# ART-Pi_Power.net
KiCad netlist of a schematic drawn in Altium Designer
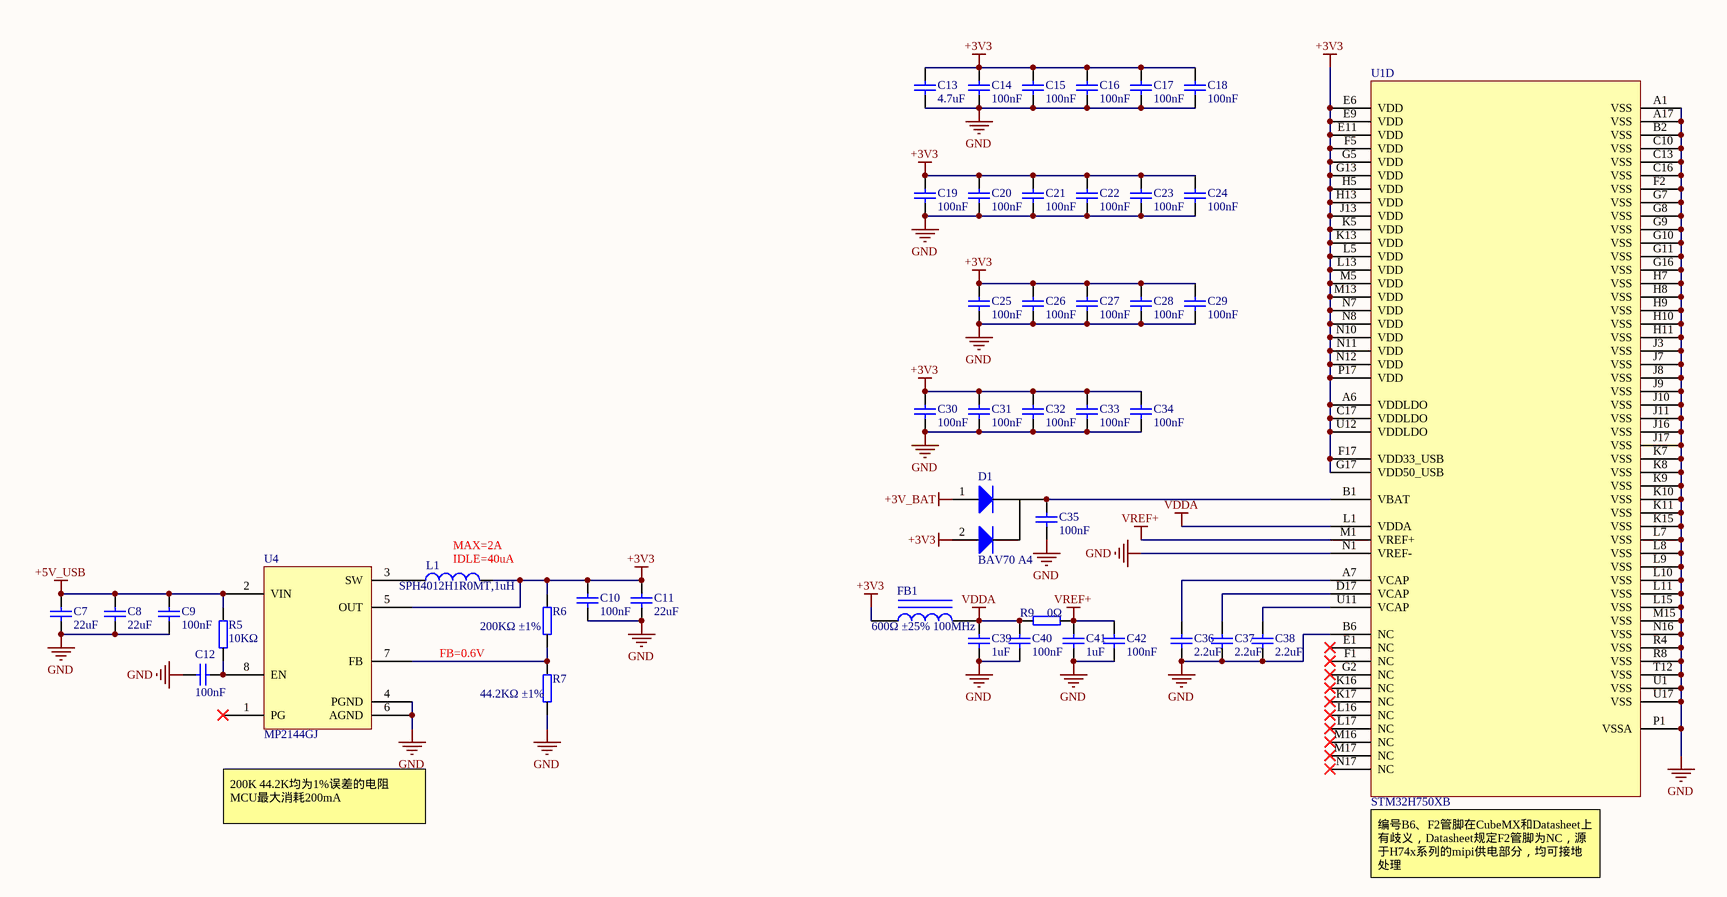
[diagram p0: ART-Pi_Power.SchDoc]

(export (version "E")
  (design (tool "Eeschema 10.0.6"))
  (components
    (comp (ref "C7")
      (value "22uF")
      (footprint "0603_C")
      (description "Capacitor")
      (fields (field (name "PUBLISHER") "Altium Limited"))
      (libsource (lib "ART-Pi_STM32H750_COPY") (part "Cap"))
    )
    (comp (ref "C8")
      (value "22uF")
      (footprint "0603_C")
      (description "Capacitor")
      (fields (field (name "PUBLISHER") "Altium Limited"))
      (libsource (lib "ART-Pi_STM32H750_COPY") (part "Cap"))
    )
    (comp (ref "C9")
      (value "100nF")
      (footprint "0402_C")
      (description "Capacitor")
      (fields (field (name "PUBLISHER") "Altium Limited"))
      (libsource (lib "ART-Pi_STM32H750_COPY") (part "Cap"))
    )
    (comp (ref "C10")
      (value "100nF")
      (footprint "0402_C")
      (description "Capacitor")
      (fields (field (name "PUBLISHER") "Altium Limited"))
      (libsource (lib "ART-Pi_STM32H750_COPY") (part "Cap"))
    )
    (comp (ref "C11")
      (value "22uF")
      (footprint "0603_C")
      (description "Capacitor")
      (fields (field (name "PUBLISHER") "Altium Limited"))
      (libsource (lib "ART-Pi_STM32H750_COPY") (part "Cap"))
    )
    (comp (ref "C12")
      (value "100nF")
      (footprint "0402_C")
      (description "Capacitor")
      (fields (field (name "PUBLISHER") "Altium Limited"))
      (libsource (lib "ART-Pi_STM32H750_COPY") (part "Cap"))
    )
    (comp (ref "C13")
      (value "4.7uF")
      (footprint "0402_C")
      (description "Capacitor")
      (fields (field (name "PUBLISHER") "Altium Limited"))
      (libsource (lib "ART-Pi_STM32H750_COPY") (part "Cap"))
    )
    (comp (ref "C14")
      (value "100nF")
      (footprint "0402_C")
      (description "Capacitor")
      (fields (field (name "PUBLISHER") "Altium Limited"))
      (libsource (lib "ART-Pi_STM32H750_COPY") (part "Cap"))
    )
    (comp (ref "C15")
      (value "100nF")
      (footprint "0402_C")
      (description "Capacitor")
      (fields (field (name "PUBLISHER") "Altium Limited"))
      (libsource (lib "ART-Pi_STM32H750_COPY") (part "Cap"))
    )
    (comp (ref "C16")
      (value "100nF")
      (footprint "0402_C")
      (description "Capacitor")
      (fields (field (name "PUBLISHER") "Altium Limited"))
      (libsource (lib "ART-Pi_STM32H750_COPY") (part "Cap"))
    )
    (comp (ref "C17")
      (value "100nF")
      (footprint "0402_C")
      (description "Capacitor")
      (fields (field (name "PUBLISHER") "Altium Limited"))
      (libsource (lib "ART-Pi_STM32H750_COPY") (part "Cap"))
    )
    (comp (ref "C18")
      (value "100nF")
      (footprint "0402_C")
      (description "Capacitor")
      (fields (field (name "PUBLISHER") "Altium Limited"))
      (libsource (lib "ART-Pi_STM32H750_COPY") (part "Cap"))
    )
    (comp (ref "C19")
      (value "100nF")
      (footprint "0402_C")
      (description "Capacitor")
      (fields (field (name "PUBLISHER") "Altium Limited"))
      (libsource (lib "ART-Pi_STM32H750_COPY") (part "Cap"))
    )
    (comp (ref "C20")
      (value "100nF")
      (footprint "0402_C")
      (description "Capacitor")
      (fields (field (name "PUBLISHER") "Altium Limited"))
      (libsource (lib "ART-Pi_STM32H750_COPY") (part "Cap"))
    )
    (comp (ref "C21")
      (value "100nF")
      (footprint "0402_C")
      (description "Capacitor")
      (fields (field (name "PUBLISHER") "Altium Limited"))
      (libsource (lib "ART-Pi_STM32H750_COPY") (part "Cap"))
    )
    (comp (ref "C22")
      (value "100nF")
      (footprint "0402_C")
      (description "Capacitor")
      (fields (field (name "PUBLISHER") "Altium Limited"))
      (libsource (lib "ART-Pi_STM32H750_COPY") (part "Cap"))
    )
    (comp (ref "C23")
      (value "100nF")
      (footprint "0402_C")
      (description "Capacitor")
      (fields (field (name "PUBLISHER") "Altium Limited"))
      (libsource (lib "ART-Pi_STM32H750_COPY") (part "Cap"))
    )
    (comp (ref "C24")
      (value "100nF")
      (footprint "0402_C")
      (description "Capacitor")
      (fields (field (name "PUBLISHER") "Altium Limited"))
      (libsource (lib "ART-Pi_STM32H750_COPY") (part "Cap"))
    )
    (comp (ref "C25")
      (value "100nF")
      (footprint "0402_C")
      (description "Capacitor")
      (fields (field (name "PUBLISHER") "Altium Limited"))
      (libsource (lib "ART-Pi_STM32H750_COPY") (part "Cap"))
    )
    (comp (ref "C26")
      (value "100nF")
      (footprint "0402_C")
      (description "Capacitor")
      (fields (field (name "PUBLISHER") "Altium Limited"))
      (libsource (lib "ART-Pi_STM32H750_COPY") (part "Cap"))
    )
    (comp (ref "C27")
      (value "100nF")
      (footprint "0402_C")
      (description "Capacitor")
      (fields (field (name "PUBLISHER") "Altium Limited"))
      (libsource (lib "ART-Pi_STM32H750_COPY") (part "Cap"))
    )
    (comp (ref "C28")
      (value "100nF")
      (footprint "0402_C")
      (description "Capacitor")
      (fields (field (name "PUBLISHER") "Altium Limited"))
      (libsource (lib "ART-Pi_STM32H750_COPY") (part "Cap"))
    )
    (comp (ref "C29")
      (value "100nF")
      (footprint "0402_C")
      (description "Capacitor")
      (fields (field (name "PUBLISHER") "Altium Limited"))
      (libsource (lib "ART-Pi_STM32H750_COPY") (part "Cap"))
    )
    (comp (ref "C30")
      (value "100nF")
      (footprint "0402_C")
      (description "Capacitor")
      (fields (field (name "PUBLISHER") "Altium Limited"))
      (libsource (lib "ART-Pi_STM32H750_COPY") (part "Cap"))
    )
    (comp (ref "C31")
      (value "100nF")
      (footprint "0402_C")
      (description "Capacitor")
      (fields (field (name "PUBLISHER") "Altium Limited"))
      (libsource (lib "ART-Pi_STM32H750_COPY") (part "Cap"))
    )
    (comp (ref "C32")
      (value "100nF")
      (footprint "0402_C")
      (description "Capacitor")
      (fields (field (name "PUBLISHER") "Altium Limited"))
      (libsource (lib "ART-Pi_STM32H750_COPY") (part "Cap"))
    )
    (comp (ref "C33")
      (value "100nF")
      (footprint "0402_C")
      (description "Capacitor")
      (fields (field (name "PUBLISHER") "Altium Limited"))
      (libsource (lib "ART-Pi_STM32H750_COPY") (part "Cap"))
    )
    (comp (ref "C34")
      (value "100nF")
      (footprint "0402_C")
      (description "Capacitor")
      (fields (field (name "PUBLISHER") "Altium Limited"))
      (libsource (lib "ART-Pi_STM32H750_COPY") (part "Cap"))
    )
    (comp (ref "C35")
      (value "100nF")
      (footprint "0402_C")
      (description "Capacitor")
      (fields (field (name "PUBLISHER") "Altium Limited"))
      (libsource (lib "ART-Pi_STM32H750_COPY") (part "Cap"))
    )
    (comp (ref "C36")
      (value "2.2uF")
      (footprint "0402_C")
      (description "Capacitor")
      (fields (field (name "PUBLISHER") "Altium Limited"))
      (libsource (lib "ART-Pi_STM32H750_COPY") (part "Cap"))
    )
    (comp (ref "C37")
      (value "2.2uF")
      (footprint "0402_C")
      (description "Capacitor")
      (fields (field (name "PUBLISHER") "Altium Limited"))
      (libsource (lib "ART-Pi_STM32H750_COPY") (part "Cap"))
    )
    (comp (ref "C38")
      (value "2.2uF")
      (footprint "0402_C")
      (description "Capacitor")
      (fields (field (name "PUBLISHER") "Altium Limited"))
      (libsource (lib "ART-Pi_STM32H750_COPY") (part "Cap"))
    )
    (comp (ref "C39")
      (value "1uF")
      (footprint "0402_C")
      (description "Capacitor")
      (fields (field (name "PUBLISHER") "Altium Limited"))
      (libsource (lib "ART-Pi_STM32H750_COPY") (part "Cap"))
    )
    (comp (ref "C40")
      (value "100nF")
      (footprint "0402_C")
      (description "Capacitor")
      (fields (field (name "PUBLISHER") "Altium Limited"))
      (libsource (lib "ART-Pi_STM32H750_COPY") (part "Cap"))
    )
    (comp (ref "C41")
      (value "1uF")
      (footprint "0402_C")
      (description "Capacitor")
      (fields (field (name "PUBLISHER") "Altium Limited"))
      (libsource (lib "ART-Pi_STM32H750_COPY") (part "Cap"))
    )
    (comp (ref "C42")
      (value "100nF")
      (footprint "0402_C")
      (description "Capacitor")
      (fields (field (name "PUBLISHER") "Altium Limited"))
      (libsource (lib "ART-Pi_STM32H750_COPY") (part "Cap"))
    )
    (comp (ref "D1")
      (value "BAV70 A4")
      (footprint "SOT23_P")
      (libsource (lib "ART-Pi_STM32H750_COPY") (part "BAV70 A4"))
    )
    (comp (ref "FB1")
      (value "600Ω ±25% 100MHz")
      (footprint "0402_R")
      (description "Magnetic-Core Inductor")
      (fields (field (name "Comment") "Inductor Iron") (field (name "PUBLISHER") "Altium Limited"))
      (libsource (lib "Miscellaneous Devices") (part "Inductor Iron"))
    )
    (comp (ref "L1")
      (value "SPH4012H1R0MT,1uH")
      (footprint "SPH4012H1R0MT")
      (description "Inductor")
      (fields (field (name "PUBLISHER") "Altium Limited"))
      (libsource (lib "ART-Pi_STM32H750_COPY") (part "Inductor"))
    )
    (comp (ref "R5")
      (value "10KΩ")
      (footprint "0402_R")
      (description "Resister")
      (libsource (lib "ART-Pi_STM32H750_COPY") (part "Res"))
    )
    (comp (ref "R6")
      (value "200KΩ ±1%")
      (footprint "0402_R")
      (description "Resister")
      (libsource (lib "ART-Pi_STM32H750_COPY") (part "Res"))
    )
    (comp (ref "R7")
      (value "44.2KΩ ±1%")
      (footprint "0402_R")
      (description "Resister")
      (libsource (lib "ART-Pi_STM32H750_COPY") (part "Res"))
    )
    (comp (ref "R9")
      (value "0Ω")
      (footprint "0402_R")
      (description "Resister")
      (libsource (lib "ART-Pi_STM32H750_COPY") (part "Res"))
    )
    (comp (ref "U1")
      (value "STM32H750XB")
      (footprint "TFBGA240+25")
      (libsource (lib "ART-Pi_STM32H750_COPY") (part "STM32H750XB"))
    )
    (comp (ref "U4")
      (value "MP2144GJ")
      (footprint "TSOP23-8")
      (libsource (lib "ART-Pi_STM32H750_COPY") (part "MP2144GJ"))
    )
  )
  (nets
    (net (code "1") (name "+3V3") (class "Default")
      (node (ref "C10") (pin "2") (pinfunction "2_2") (pintype "passive"))
      (node (ref "C11") (pin "2") (pinfunction "2_2") (pintype "passive"))
      (node (ref "C13") (pin "2") (pinfunction "2_2") (pintype "passive"))
      (node (ref "C14") (pin "2") (pinfunction "2_2") (pintype "passive"))
      (node (ref "C15") (pin "2") (pinfunction "2_2") (pintype "passive"))
      (node (ref "C16") (pin "2") (pinfunction "2_2") (pintype "passive"))
      (node (ref "C17") (pin "2") (pinfunction "2_2") (pintype "passive"))
      (node (ref "C18") (pin "2") (pinfunction "2_2") (pintype "passive"))
      (node (ref "C19") (pin "2") (pinfunction "2_2") (pintype "passive"))
      (node (ref "C20") (pin "2") (pinfunction "2_2") (pintype "passive"))
      (node (ref "C21") (pin "2") (pinfunction "2_2") (pintype "passive"))
      (node (ref "C22") (pin "2") (pinfunction "2_2") (pintype "passive"))
      (node (ref "C23") (pin "2") (pinfunction "2_2") (pintype "passive"))
      (node (ref "C24") (pin "2") (pinfunction "2_2") (pintype "passive"))
      (node (ref "C25") (pin "2") (pinfunction "2_2") (pintype "passive"))
      (node (ref "C26") (pin "2") (pinfunction "2_2") (pintype "passive"))
      (node (ref "C27") (pin "2") (pinfunction "2_2") (pintype "passive"))
      (node (ref "C28") (pin "2") (pinfunction "2_2") (pintype "passive"))
      (node (ref "C29") (pin "2") (pinfunction "2_2") (pintype "passive"))
      (node (ref "C30") (pin "2") (pinfunction "2_2") (pintype "passive"))
      (node (ref "C31") (pin "2") (pinfunction "2_2") (pintype "passive"))
      (node (ref "C32") (pin "2") (pinfunction "2_2") (pintype "passive"))
      (node (ref "C33") (pin "2") (pinfunction "2_2") (pintype "passive"))
      (node (ref "C34") (pin "2") (pinfunction "2_2") (pintype "passive"))
      (node (ref "D1") (pin "2") (pinfunction "2_2") (pintype "passive"))
      (node (ref "FB1") (pin "1") (pinfunction "1_1") (pintype "passive"))
      (node (ref "L1") (pin "2") (pinfunction "2_2") (pintype "passive"))
      (node (ref "R6") (pin "2") (pinfunction "2_2") (pintype "passive"))
      (node (ref "U1") (pin "A6") (pinfunction "VDDLDO_A6") (pintype "passive"))
      (node (ref "U1") (pin "C17") (pinfunction "VDDLDO_C17") (pintype "passive"))
      (node (ref "U1") (pin "E11") (pinfunction "VDD_E11") (pintype "passive"))
      (node (ref "U1") (pin "E6") (pinfunction "VDD_E6") (pintype "passive"))
      (node (ref "U1") (pin "E9") (pinfunction "VDD_E9") (pintype "passive"))
      (node (ref "U1") (pin "F17") (pinfunction "VDD33_USB_F17") (pintype "passive"))
      (node (ref "U1") (pin "F5") (pinfunction "VDD_F5") (pintype "passive"))
      (node (ref "U1") (pin "G13") (pinfunction "VDD_G13") (pintype "passive"))
      (node (ref "U1") (pin "G17") (pinfunction "VDD50_USB_G17") (pintype "passive"))
      (node (ref "U1") (pin "G5") (pinfunction "VDD_G5") (pintype "passive"))
      (node (ref "U1") (pin "H13") (pinfunction "VDD_H13") (pintype "passive"))
      (node (ref "U1") (pin "H5") (pinfunction "VDD_H5") (pintype "passive"))
      (node (ref "U1") (pin "J13") (pinfunction "VDD_J13") (pintype "passive"))
      (node (ref "U1") (pin "K13") (pinfunction "VDD_K13") (pintype "passive"))
      (node (ref "U1") (pin "K5") (pinfunction "VDD_K5") (pintype "passive"))
      (node (ref "U1") (pin "L13") (pinfunction "VDD_L13") (pintype "passive"))
      (node (ref "U1") (pin "L5") (pinfunction "VDD_L5") (pintype "passive"))
      (node (ref "U1") (pin "M13") (pinfunction "VDD_M13") (pintype "passive"))
      (node (ref "U1") (pin "M5") (pinfunction "VDD_M5") (pintype "passive"))
      (node (ref "U1") (pin "N10") (pinfunction "VDD_N10") (pintype "passive"))
      (node (ref "U1") (pin "N11") (pinfunction "VDD_N11") (pintype "passive"))
      (node (ref "U1") (pin "N12") (pinfunction "VDD_N12") (pintype "passive"))
      (node (ref "U1") (pin "N7") (pinfunction "VDD_N7") (pintype "passive"))
      (node (ref "U1") (pin "N8") (pinfunction "VDD_N8") (pintype "passive"))
      (node (ref "U1") (pin "P17") (pinfunction "VDD_P17") (pintype "passive"))
      (node (ref "U1") (pin "U12") (pinfunction "VDDLDO_U12") (pintype "passive"))
      (node (ref "U4") (pin "5") (pinfunction "OUT_5") (pintype "passive"))
    )
    (net (code "2") (name "+3V_BAT") (class "Default")
      (node (ref "D1") (pin "1") (pinfunction "1_1") (pintype "passive"))
    )
    (net (code "3") (name "+5V_USB") (class "Default")
      (node (ref "C7") (pin "2") (pinfunction "2_2") (pintype "passive"))
      (node (ref "C8") (pin "2") (pinfunction "2_2") (pintype "passive"))
      (node (ref "C9") (pin "2") (pinfunction "2_2") (pintype "passive"))
      (node (ref "R5") (pin "2") (pinfunction "2_2") (pintype "passive"))
      (node (ref "U4") (pin "2") (pinfunction "VIN_2") (pintype "passive"))
    )
    (net (code "4") (name "GND") (class "Default")
      (node (ref "C10") (pin "1") (pinfunction "1_1") (pintype "passive"))
      (node (ref "C11") (pin "1") (pinfunction "1_1") (pintype "passive"))
      (node (ref "C12") (pin "2") (pinfunction "2_2") (pintype "passive"))
      (node (ref "C13") (pin "1") (pinfunction "1_1") (pintype "passive"))
      (node (ref "C14") (pin "1") (pinfunction "1_1") (pintype "passive"))
      (node (ref "C15") (pin "1") (pinfunction "1_1") (pintype "passive"))
      (node (ref "C16") (pin "1") (pinfunction "1_1") (pintype "passive"))
      (node (ref "C17") (pin "1") (pinfunction "1_1") (pintype "passive"))
      (node (ref "C18") (pin "1") (pinfunction "1_1") (pintype "passive"))
      (node (ref "C19") (pin "1") (pinfunction "1_1") (pintype "passive"))
      (node (ref "C20") (pin "1") (pinfunction "1_1") (pintype "passive"))
      (node (ref "C21") (pin "1") (pinfunction "1_1") (pintype "passive"))
      (node (ref "C22") (pin "1") (pinfunction "1_1") (pintype "passive"))
      (node (ref "C23") (pin "1") (pinfunction "1_1") (pintype "passive"))
      (node (ref "C24") (pin "1") (pinfunction "1_1") (pintype "passive"))
      (node (ref "C25") (pin "1") (pinfunction "1_1") (pintype "passive"))
      (node (ref "C26") (pin "1") (pinfunction "1_1") (pintype "passive"))
      (node (ref "C27") (pin "1") (pinfunction "1_1") (pintype "passive"))
      (node (ref "C28") (pin "1") (pinfunction "1_1") (pintype "passive"))
      (node (ref "C29") (pin "1") (pinfunction "1_1") (pintype "passive"))
      (node (ref "C30") (pin "1") (pinfunction "1_1") (pintype "passive"))
      (node (ref "C31") (pin "1") (pinfunction "1_1") (pintype "passive"))
      (node (ref "C32") (pin "1") (pinfunction "1_1") (pintype "passive"))
      (node (ref "C33") (pin "1") (pinfunction "1_1") (pintype "passive"))
      (node (ref "C34") (pin "1") (pinfunction "1_1") (pintype "passive"))
      (node (ref "C35") (pin "1") (pinfunction "1_1") (pintype "passive"))
      (node (ref "C36") (pin "1") (pinfunction "1_1") (pintype "passive"))
      (node (ref "C37") (pin "1") (pinfunction "1_1") (pintype "passive"))
      (node (ref "C38") (pin "1") (pinfunction "1_1") (pintype "passive"))
      (node (ref "C39") (pin "1") (pinfunction "1_1") (pintype "passive"))
      (node (ref "C40") (pin "1") (pinfunction "1_1") (pintype "passive"))
      (node (ref "C41") (pin "1") (pinfunction "1_1") (pintype "passive"))
      (node (ref "C42") (pin "1") (pinfunction "1_1") (pintype "passive"))
      (node (ref "C7") (pin "1") (pinfunction "1_1") (pintype "passive"))
      (node (ref "C8") (pin "1") (pinfunction "1_1") (pintype "passive"))
      (node (ref "C9") (pin "1") (pinfunction "1_1") (pintype "passive"))
      (node (ref "R7") (pin "1") (pinfunction "1_1") (pintype "passive"))
      (node (ref "U1") (pin "A1") (pinfunction "VSS_A1") (pintype "passive"))
      (node (ref "U1") (pin "A17") (pinfunction "VSS_A17") (pintype "passive"))
      (node (ref "U1") (pin "B2") (pinfunction "VSS_B2") (pintype "passive"))
      (node (ref "U1") (pin "B6") (pinfunction "NC_B6") (pintype "passive"))
      (node (ref "U1") (pin "C10") (pinfunction "VSS_C10") (pintype "passive"))
      (node (ref "U1") (pin "C13") (pinfunction "VSS_C13") (pintype "passive"))
      (node (ref "U1") (pin "C16") (pinfunction "VSS_C16") (pintype "passive"))
      (node (ref "U1") (pin "F2") (pinfunction "VSS_F2") (pintype "passive"))
      (node (ref "U1") (pin "G10") (pinfunction "VSS_G10") (pintype "passive"))
      (node (ref "U1") (pin "G11") (pinfunction "VSS_G11") (pintype "passive"))
      (node (ref "U1") (pin "G16") (pinfunction "VSS_G16") (pintype "passive"))
      (node (ref "U1") (pin "G7") (pinfunction "VSS_G7") (pintype "passive"))
      (node (ref "U1") (pin "G8") (pinfunction "VSS_G8") (pintype "passive"))
      (node (ref "U1") (pin "G9") (pinfunction "VSS_G9") (pintype "passive"))
      (node (ref "U1") (pin "H10") (pinfunction "VSS_H10") (pintype "passive"))
      (node (ref "U1") (pin "H11") (pinfunction "VSS_H11") (pintype "passive"))
      (node (ref "U1") (pin "H7") (pinfunction "VSS_H7") (pintype "passive"))
      (node (ref "U1") (pin "H8") (pinfunction "VSS_H8") (pintype "passive"))
      (node (ref "U1") (pin "H9") (pinfunction "VSS_H9") (pintype "passive"))
      (node (ref "U1") (pin "J10") (pinfunction "VSS_J10") (pintype "passive"))
      (node (ref "U1") (pin "J11") (pinfunction "VSS_J11") (pintype "passive"))
      (node (ref "U1") (pin "J16") (pinfunction "VSS_J16") (pintype "passive"))
      (node (ref "U1") (pin "J17") (pinfunction "VSS_J17") (pintype "passive"))
      (node (ref "U1") (pin "J3") (pinfunction "VSS_J3") (pintype "passive"))
      (node (ref "U1") (pin "J7") (pinfunction "VSS_J7") (pintype "passive"))
      (node (ref "U1") (pin "J8") (pinfunction "VSS_J8") (pintype "passive"))
      (node (ref "U1") (pin "J9") (pinfunction "VSS_J9") (pintype "passive"))
      (node (ref "U1") (pin "K10") (pinfunction "VSS_K10") (pintype "passive"))
      (node (ref "U1") (pin "K11") (pinfunction "VSS_K11") (pintype "passive"))
      (node (ref "U1") (pin "K15") (pinfunction "VSS_K15") (pintype "passive"))
      (node (ref "U1") (pin "K7") (pinfunction "VSS_K7") (pintype "passive"))
      (node (ref "U1") (pin "K8") (pinfunction "VSS_K8") (pintype "passive"))
      (node (ref "U1") (pin "K9") (pinfunction "VSS_K9") (pintype "passive"))
      (node (ref "U1") (pin "L10") (pinfunction "VSS_L10") (pintype "passive"))
      (node (ref "U1") (pin "L11") (pinfunction "VSS_L11") (pintype "passive"))
      (node (ref "U1") (pin "L15") (pinfunction "VSS_L15") (pintype "passive"))
      (node (ref "U1") (pin "L7") (pinfunction "VSS_L7") (pintype "passive"))
      (node (ref "U1") (pin "L8") (pinfunction "VSS_L8") (pintype "passive"))
      (node (ref "U1") (pin "L9") (pinfunction "VSS_L9") (pintype "passive"))
      (node (ref "U1") (pin "M15") (pinfunction "VSS_M15") (pintype "passive"))
      (node (ref "U1") (pin "N1") (pinfunction "VREF-_N1") (pintype "passive"))
      (node (ref "U1") (pin "N16") (pinfunction "VSS_N16") (pintype "passive"))
      (node (ref "U1") (pin "P1") (pinfunction "VSSA_P1") (pintype "passive"))
      (node (ref "U1") (pin "R4") (pinfunction "VSS_R4") (pintype "passive"))
      (node (ref "U1") (pin "R8") (pinfunction "VSS_R8") (pintype "passive"))
      (node (ref "U1") (pin "T12") (pinfunction "VSS_T12") (pintype "passive"))
      (node (ref "U1") (pin "U1") (pinfunction "VSS_U1") (pintype "passive"))
      (node (ref "U1") (pin "U17") (pinfunction "VSS_U17") (pintype "passive"))
      (node (ref "U4") (pin "4") (pinfunction "PGND_4") (pintype "passive"))
      (node (ref "U4") (pin "6") (pinfunction "AGND_6") (pintype "passive"))
    )
    (net (code "5") (name "Net-(C36-Pad2)") (class "Default")
      (node (ref "C36") (pin "2") (pinfunction "2_2") (pintype "passive"))
      (node (ref "U1") (pin "A7") (pinfunction "VCAP_A7") (pintype "passive"))
    )
    (net (code "6") (name "Net-(C37-Pad2)") (class "Default")
      (node (ref "C37") (pin "2") (pinfunction "2_2") (pintype "passive"))
      (node (ref "U1") (pin "D17") (pinfunction "VCAP_D17") (pintype "passive"))
    )
    (net (code "7") (name "Net-(C38-Pad2)") (class "Default")
      (node (ref "C38") (pin "2") (pinfunction "2_2") (pintype "passive"))
      (node (ref "U1") (pin "U11") (pinfunction "VCAP_U11") (pintype "passive"))
    )
    (net (code "8") (name "Net-(U1D-VBAT)") (class "Default")
      (node (ref "C35") (pin "2") (pinfunction "2_2") (pintype "passive"))
      (node (ref "D1") (pin "3") (pinfunction "3_3") (pintype "passive"))
      (node (ref "U1") (pin "B1") (pinfunction "VBAT_B1") (pintype "passive"))
    )
    (net (code "9") (name "Net-(U4-EN)") (class "Default")
      (node (ref "C12") (pin "1") (pinfunction "1_1") (pintype "passive"))
      (node (ref "R5") (pin "1") (pinfunction "1_1") (pintype "passive"))
      (node (ref "U4") (pin "8") (pinfunction "EN_8") (pintype "passive"))
    )
    (net (code "10") (name "Net-(U4-FB)") (class "Default")
      (node (ref "R6") (pin "1") (pinfunction "1_1") (pintype "passive"))
      (node (ref "R7") (pin "2") (pinfunction "2_2") (pintype "passive"))
      (node (ref "U4") (pin "7") (pinfunction "FB_7") (pintype "passive"))
    )
    (net (code "11") (name "Net-(U4-SW)") (class "Default")
      (node (ref "L1") (pin "1") (pinfunction "1_1") (pintype "passive"))
      (node (ref "U4") (pin "3") (pinfunction "SW_3") (pintype "passive"))
    )
    (net (code "12") (name "VDDA") (class "Default")
      (node (ref "C39") (pin "2") (pinfunction "2_2") (pintype "passive"))
      (node (ref "C40") (pin "2") (pinfunction "2_2") (pintype "passive"))
      (node (ref "FB1") (pin "2") (pinfunction "2_2") (pintype "passive"))
      (node (ref "R9") (pin "2") (pinfunction "2_2") (pintype "passive"))
      (node (ref "U1") (pin "L1") (pinfunction "VDDA_L1") (pintype "passive"))
    )
    (net (code "13") (name "VREF+") (class "Default")
      (node (ref "C41") (pin "2") (pinfunction "2_2") (pintype "passive"))
      (node (ref "C42") (pin "2") (pinfunction "2_2") (pintype "passive"))
      (node (ref "R9") (pin "1") (pinfunction "1_1") (pintype "passive"))
      (node (ref "U1") (pin "M1") (pinfunction "VREF+_M1") (pintype "passive"))
    )
    (net (code "14") (name "unconnected-(U1D-NC-PadE1)") (class "Default")
      (node (ref "U1") (pin "E1") (pinfunction "NC_E1") (pintype "passive+no_connect"))
    )
    (net (code "15") (name "unconnected-(U1D-NC-PadF1)") (class "Default")
      (node (ref "U1") (pin "F1") (pinfunction "NC_F1") (pintype "passive+no_connect"))
    )
    (net (code "16") (name "unconnected-(U1D-NC-PadG2)") (class "Default")
      (node (ref "U1") (pin "G2") (pinfunction "NC_G2") (pintype "passive+no_connect"))
    )
    (net (code "17") (name "unconnected-(U1D-NC-PadK16)") (class "Default")
      (node (ref "U1") (pin "K16") (pinfunction "NC_K16") (pintype "passive+no_connect"))
    )
    (net (code "18") (name "unconnected-(U1D-NC-PadK17)") (class "Default")
      (node (ref "U1") (pin "K17") (pinfunction "NC_K17") (pintype "passive+no_connect"))
    )
    (net (code "19") (name "unconnected-(U1D-NC-PadL16)") (class "Default")
      (node (ref "U1") (pin "L16") (pinfunction "NC_L16") (pintype "passive+no_connect"))
    )
    (net (code "20") (name "unconnected-(U1D-NC-PadL17)") (class "Default")
      (node (ref "U1") (pin "L17") (pinfunction "NC_L17") (pintype "passive+no_connect"))
    )
    (net (code "21") (name "unconnected-(U1D-NC-PadM16)") (class "Default")
      (node (ref "U1") (pin "M16") (pinfunction "NC_M16") (pintype "passive+no_connect"))
    )
    (net (code "22") (name "unconnected-(U1D-NC-PadM17)") (class "Default")
      (node (ref "U1") (pin "M17") (pinfunction "NC_M17") (pintype "passive+no_connect"))
    )
    (net (code "23") (name "unconnected-(U1D-NC-PadN17)") (class "Default")
      (node (ref "U1") (pin "N17") (pinfunction "NC_N17") (pintype "passive+no_connect"))
    )
    (net (code "24") (name "unconnected-(U4-PG-Pad1)") (class "Default")
      (node (ref "U4") (pin "1") (pinfunction "PG_1") (pintype "passive+no_connect"))
    )
  )
)
